# SHABlindController.net
KiCad netlist of a schematic drawn in EAGLE
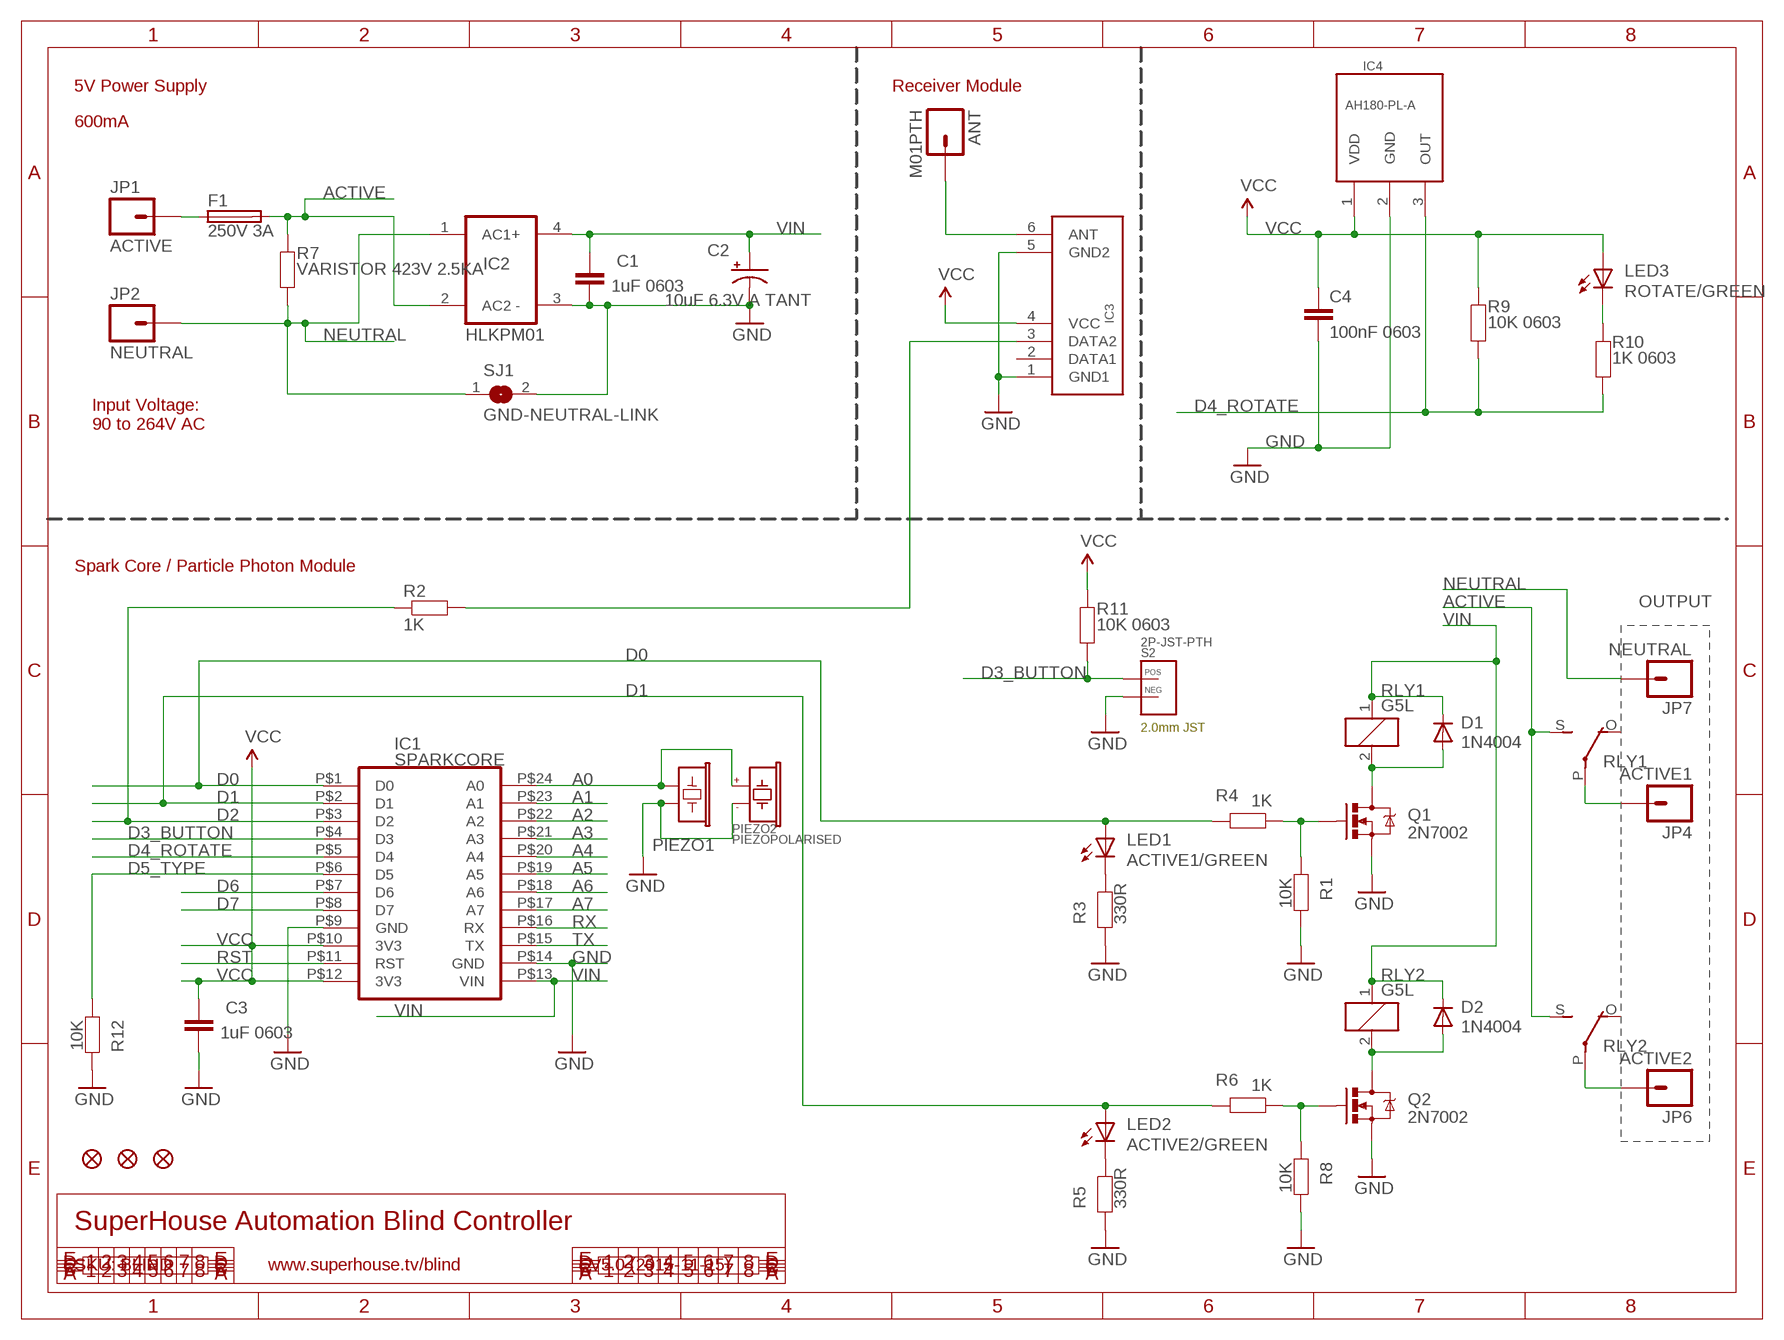
[diagram p0: schematic, sheet 1]

(export (version "E")
  (design (tool "Eeschema 10.0.6"))
  (components
    (comp (ref "ANT")
      (value "M01PTH")
      (footprint "eagle-import:1X01")
      (libsource (lib "eagle-import") (part "M01PTH"))
    )
    (comp (ref "C1")
      (value "1uF 0603")
      (footprint "eagle-import:0603@1")
      (libsource (lib "eagle-import") (part "CAP0603"))
    )
    (comp (ref "C2")
      (value "10uF 6.3V A TANT")
      (footprint "eagle-import:EIA3216")
      (libsource (lib "eagle-import") (part "CAP_POL1206"))
    )
    (comp (ref "C3")
      (value "1uF 0603")
      (footprint "eagle-import:0603@1")
      (libsource (lib "eagle-import") (part "CAP0603"))
    )
    (comp (ref "C4")
      (value "100nF 0603")
      (footprint "eagle-import:0603")
      (libsource (lib "eagle-import") (part "freetronics-master-v1.1_CAP0603"))
    )
    (comp (ref "D1")
      (value "1N4004")
      (footprint "eagle-import:SMB-DIODE")
      (libsource (lib "eagle-import") (part "DIODESMB"))
    )
    (comp (ref "D2")
      (value "1N4004")
      (footprint "eagle-import:SMB-DIODE")
      (libsource (lib "eagle-import") (part "DIODESMB"))
    )
    (comp (ref "F1")
      (value "250V 3A")
      (footprint "eagle-import:PICOFUSE")
      (libsource (lib "eagle-import") (part "PICOFUSEH"))
    )
    (comp (ref "FID1")
      (value "FIDUCIAL1X2.5")
      (footprint "eagle-import:FIDUCIAL-1X2.5")
      (libsource (lib "eagle-import") (part "FIDUCIAL1X2.5"))
    )
    (comp (ref "FID2")
      (value "FIDUCIAL1X2.5")
      (footprint "eagle-import:FIDUCIAL-1X2.5")
      (libsource (lib "eagle-import") (part "FIDUCIAL1X2.5"))
    )
    (comp (ref "FID3")
      (value "FIDUCIAL1X2.5")
      (footprint "eagle-import:FIDUCIAL-1X2.5")
      (libsource (lib "eagle-import") (part "FIDUCIAL1X2.5"))
    )
    (comp (ref "IC1")
      (value "SPARKCORE")
      (footprint "eagle-import:SPARKCORE")
      (libsource (lib "eagle-import") (part "SPARKCORE"))
    )
    (comp (ref "IC2")
      (value "HLKPM01")
      (footprint "eagle-import:HLKPM01")
      (libsource (lib "eagle-import") (part "HLKPM01"))
    )
    (comp (ref "IC3")
      (value "RXB1")
      (footprint "eagle-import:RX-B1-SHORT-FLAT")
      (libsource (lib "eagle-import") (part "RXB1SHORTFLAT"))
    )
    (comp (ref "IC4")
      (value "AH180-PL-A")
      (footprint "eagle-import:TO92FLATUP")
      (libsource (lib "eagle-import") (part "US1881TO92"))
    )
    (comp (ref "JP1")
      (value "ACTIVE")
      (footprint "eagle-import:1X01LARGE")
      (libsource (lib "eagle-import") (part "M01PTH_LARGE"))
    )
    (comp (ref "JP2")
      (value "NEUTRAL")
      (footprint "eagle-import:1X01LARGE")
      (libsource (lib "eagle-import") (part "M01PTH_LARGE"))
    )
    (comp (ref "JP4")
      (value "ACTIVE1")
      (footprint "eagle-import:1X01LARGE")
      (libsource (lib "eagle-import") (part "M01PTH_LARGE"))
    )
    (comp (ref "JP6")
      (value "ACTIVE2")
      (footprint "eagle-import:1X01LARGE")
      (libsource (lib "eagle-import") (part "M01PTH_LARGE"))
    )
    (comp (ref "JP7")
      (value "NEUTRAL")
      (footprint "eagle-import:1X01LARGE")
      (libsource (lib "eagle-import") (part "M01PTH_LARGE"))
    )
    (comp (ref "LED1")
      (value "ACTIVE1/GREEN")
      (footprint "eagle-import:LED-0603")
      (libsource (lib "eagle-import") (part "LED0603"))
    )
    (comp (ref "LED2")
      (value "ACTIVE2/GREEN")
      (footprint "eagle-import:LED-0603")
      (libsource (lib "eagle-import") (part "LED0603"))
    )
    (comp (ref "LED3")
      (value "ROTATE/GREEN")
      (footprint "eagle-import:LED-0603")
      (libsource (lib "eagle-import") (part "LED0603"))
    )
    (comp (ref "PIEZO1")
      (value "BUZZERSMD12X12")
      (footprint "eagle-import:BUZZER-12X12-SMT")
      (libsource (lib "eagle-import") (part "BUZZERSMD12X12"))
    )
    (comp (ref "PIEZO2")
      (value "PIEZOPOLARISED")
      (footprint "eagle-import:PIEZO12MMWIDEPOLARISED")
      (libsource (lib "eagle-import") (part "PIEZOPOLARISED"))
    )
    (comp (ref "Q1")
      (value "2N7002")
      (footprint "eagle-import:SOT23-3")
      (libsource (lib "eagle-import") (part "MOSFET-NCHANNELSMD"))
    )
    (comp (ref "Q2")
      (value "2N7002")
      (footprint "eagle-import:SOT23-3")
      (libsource (lib "eagle-import") (part "MOSFET-NCHANNELSMD"))
    )
    (comp (ref "R1")
      (value "10K")
      (footprint "eagle-import:0603")
      (libsource (lib "eagle-import") (part "RESISTOR0603"))
    )
    (comp (ref "R2")
      (value "1K")
      (footprint "eagle-import:0603")
      (libsource (lib "eagle-import") (part "RESISTOR0603"))
    )
    (comp (ref "R3")
      (value "330R")
      (footprint "eagle-import:0603")
      (libsource (lib "eagle-import") (part "RESISTOR0603"))
    )
    (comp (ref "R4")
      (value "1K")
      (footprint "eagle-import:0603")
      (libsource (lib "eagle-import") (part "RESISTOR0603"))
    )
    (comp (ref "R5")
      (value "330R")
      (footprint "eagle-import:0603")
      (libsource (lib "eagle-import") (part "RESISTOR0603"))
    )
    (comp (ref "R6")
      (value "1K")
      (footprint "eagle-import:0603")
      (libsource (lib "eagle-import") (part "RESISTOR0603"))
    )
    (comp (ref "R7")
      (value "VARISTOR 423V 2.5KA")
      (footprint "eagle-import:AXIAL-0.3")
      (libsource (lib "eagle-import") (part "freetronics-master-v1.1_RESISTORPTH1"))
    )
    (comp (ref "R8")
      (value "10K")
      (footprint "eagle-import:0603")
      (libsource (lib "eagle-import") (part "RESISTOR0603"))
    )
    (comp (ref "R9")
      (value "10K 0603")
      (footprint "eagle-import:0603")
      (libsource (lib "eagle-import") (part "freetronics-master-v1_RESISTOR0603"))
    )
    (comp (ref "R10")
      (value "1K 0603")
      (footprint "eagle-import:0603")
      (libsource (lib "eagle-import") (part "freetronics-master-v1_RESISTOR0603"))
    )
    (comp (ref "R11")
      (value "10K 0603")
      (footprint "eagle-import:0603")
      (libsource (lib "eagle-import") (part "freetronics-master-v1_RESISTOR0603"))
    )
    (comp (ref "R12")
      (value "10K")
      (footprint "eagle-import:0603")
      (libsource (lib "eagle-import") (part "RESISTOR0603"))
    )
    (comp (ref "RLY1")
      (value "G5L")
      (footprint "eagle-import:G5LE")
      (libsource (lib "eagle-import") (part "G5L"))
    )
    (comp (ref "RLY2")
      (value "G5L")
      (footprint "eagle-import:G5LE")
      (libsource (lib "eagle-import") (part "G5L"))
    )
    (comp (ref "S2")
      (value "2P-JST-PTH")
      (footprint "eagle-import:JST-2MM-TH-RA")
      (libsource (lib "eagle-import") (part "2P-JST-TH-RAPTH"))
    )
    (comp (ref "SJ1")
      (value "GND-NEUTRAL-LINK")
      (footprint "eagle-import:SJ")
      (libsource (lib "eagle-import") (part "SJ"))
    )
  )
  (nets
    (net (code "1") (name "/A0") (class "Default")
      (node (ref "IC1") (pin "P$24") (pinfunction "A0_P$24") (pintype "bidirectional"))
      (node (ref "PIEZO1") (pin "1") (pinfunction "1_1") (pintype "passive"))
      (node (ref "PIEZO2") (pin "1") (pinfunction "+_1") (pintype "bidirectional"))
    )
    (net (code "2") (name "/A1") (class "Default")
      (node (ref "IC1") (pin "P$23") (pinfunction "A1_P$23") (pintype "bidirectional"))
    )
    (net (code "3") (name "/A2") (class "Default")
      (node (ref "IC1") (pin "P$22") (pinfunction "A2_P$22") (pintype "bidirectional"))
    )
    (net (code "4") (name "/A3") (class "Default")
      (node (ref "IC1") (pin "P$21") (pinfunction "A3_P$21") (pintype "bidirectional"))
    )
    (net (code "5") (name "/A4") (class "Default")
      (node (ref "IC1") (pin "P$20") (pinfunction "A4_P$20") (pintype "bidirectional"))
    )
    (net (code "6") (name "/A5") (class "Default")
      (node (ref "IC1") (pin "P$19") (pinfunction "A5_P$19") (pintype "bidirectional"))
    )
    (net (code "7") (name "/A6") (class "Default")
      (node (ref "IC1") (pin "P$18") (pinfunction "A6_P$18") (pintype "bidirectional"))
    )
    (net (code "8") (name "/A7") (class "Default")
      (node (ref "IC1") (pin "P$17") (pinfunction "A7_P$17") (pintype "bidirectional"))
    )
    (net (code "9") (name "/ACTIVE") (class "Default")
      (node (ref "F1") (pin "2") (pinfunction "2_2") (pintype "passive"))
      (node (ref "IC2") (pin "2") (pinfunction "AC2_2") (pintype "bidirectional"))
      (node (ref "R7") (pin "P$2") (pinfunction "2_P$2") (pintype "passive"))
      (node (ref "RLY1") (pin "S") (pinfunction "S_S") (pintype "passive"))
      (node (ref "RLY2") (pin "S") (pinfunction "S_S") (pintype "passive"))
    )
    (net (code "10") (name "/D0") (class "Default")
      (node (ref "IC1") (pin "P$1") (pinfunction "D0_P$1") (pintype "bidirectional"))
      (node (ref "LED1") (pin "A") (pinfunction "A_A") (pintype "passive"))
      (node (ref "R4") (pin "2") (pinfunction "2_2") (pintype "passive"))
    )
    (net (code "11") (name "/D1") (class "Default")
      (node (ref "IC1") (pin "P$2") (pinfunction "D1_P$2") (pintype "bidirectional"))
      (node (ref "LED2") (pin "A") (pinfunction "A_A") (pintype "passive"))
      (node (ref "R6") (pin "2") (pinfunction "2_2") (pintype "passive"))
    )
    (net (code "12") (name "/D2") (class "Default")
      (node (ref "IC1") (pin "P$3") (pinfunction "D2_P$3") (pintype "bidirectional"))
      (node (ref "R2") (pin "1") (pinfunction "1_1") (pintype "passive"))
    )
    (net (code "13") (name "/D3_BUTTON") (class "Default")
      (node (ref "IC1") (pin "P$4") (pinfunction "D3_P$4") (pintype "bidirectional"))
      (node (ref "R11") (pin "1") (pinfunction "1_1") (pintype "passive"))
      (node (ref "S2") (pin "POS") (pinfunction "POS_POS") (pintype "power_in"))
    )
    (net (code "14") (name "/D4_ROTATE") (class "Default")
      (node (ref "IC1") (pin "P$5") (pinfunction "D4_P$5") (pintype "bidirectional"))
      (node (ref "IC4") (pin "3") (pinfunction "OUT_3") (pintype "output"))
      (node (ref "R10") (pin "2") (pinfunction "2_2") (pintype "passive"))
      (node (ref "R9") (pin "1") (pinfunction "1_1") (pintype "passive"))
    )
    (net (code "15") (name "/D5_TYPE") (class "Default")
      (node (ref "IC1") (pin "P$6") (pinfunction "D5_P$6") (pintype "bidirectional"))
      (node (ref "R12") (pin "1") (pinfunction "1_1") (pintype "passive"))
    )
    (net (code "16") (name "/D6") (class "Default")
      (node (ref "IC1") (pin "P$7") (pinfunction "D6_P$7") (pintype "bidirectional"))
    )
    (net (code "17") (name "/D7") (class "Default")
      (node (ref "IC1") (pin "P$8") (pinfunction "D7_P$8") (pintype "bidirectional"))
    )
    (net (code "18") (name "/NEUTRAL") (class "Default")
      (node (ref "IC2") (pin "1") (pinfunction "AC1_1") (pintype "bidirectional"))
      (node (ref "JP2") (pin "1") (pinfunction "1_1") (pintype "passive"))
      (node (ref "JP7") (pin "1") (pinfunction "1_1") (pintype "passive"))
      (node (ref "R7") (pin "P$1") (pinfunction "1_P$1") (pintype "passive"))
      (node (ref "SJ1") (pin "1") (pinfunction "1_1") (pintype "passive"))
    )
    (net (code "19") (name "/RST") (class "Default")
      (node (ref "IC1") (pin "P$11") (pinfunction "RST_P$11") (pintype "bidirectional"))
    )
    (net (code "20") (name "/RX") (class "Default")
      (node (ref "IC1") (pin "P$16") (pinfunction "RX_P$16") (pintype "bidirectional"))
    )
    (net (code "21") (name "/TX") (class "Default")
      (node (ref "IC1") (pin "P$15") (pinfunction "TX_P$15") (pintype "bidirectional"))
    )
    (net (code "22") (name "/VIN") (class "Default")
      (node (ref "C1") (pin "1") (pinfunction "1_1") (pintype "passive"))
      (node (ref "C2") (pin "A") (pinfunction "+_A") (pintype "passive"))
      (node (ref "D1") (pin "C") (pinfunction "C_C") (pintype "passive"))
      (node (ref "D2") (pin "C") (pinfunction "C_C") (pintype "passive"))
      (node (ref "IC1") (pin "P$13") (pinfunction "VIN_P$13") (pintype "bidirectional"))
      (node (ref "IC2") (pin "4") (pinfunction "+_4") (pintype "bidirectional"))
      (node (ref "RLY1") (pin "1") (pinfunction "1_1") (pintype "passive"))
      (node (ref "RLY2") (pin "1") (pinfunction "1_1") (pintype "passive"))
    )
    (net (code "23") (name "GND") (class "Default")
      (node (ref "C1") (pin "2") (pinfunction "2_2") (pintype "passive"))
      (node (ref "C2") (pin "C") (pinfunction "-_C") (pintype "passive"))
      (node (ref "C3") (pin "2") (pinfunction "2_2") (pintype "passive"))
      (node (ref "C4") (pin "2") (pinfunction "2_2") (pintype "passive"))
      (node (ref "IC1") (pin "P$14") (pinfunction "GND_P$14") (pintype "bidirectional"))
      (node (ref "IC1") (pin "P$9") (pinfunction "GND_P$9") (pintype "bidirectional"))
      (node (ref "IC2") (pin "3") (pinfunction "-_3") (pintype "bidirectional"))
      (node (ref "IC3") (pin "1") (pinfunction "GND1_1") (pintype "bidirectional"))
      (node (ref "IC3") (pin "5") (pinfunction "GND2_5") (pintype "bidirectional"))
      (node (ref "IC4") (pin "2") (pinfunction "GND_2") (pintype "power_in"))
      (node (ref "PIEZO1") (pin "2") (pinfunction "2_2") (pintype "passive"))
      (node (ref "PIEZO2") (pin "2") (pinfunction "-_2") (pintype "bidirectional"))
      (node (ref "Q1") (pin "2") (pinfunction "S_2") (pintype "passive"))
      (node (ref "Q2") (pin "2") (pinfunction "S_2") (pintype "passive"))
      (node (ref "R1") (pin "2") (pinfunction "2_2") (pintype "passive"))
      (node (ref "R12") (pin "2") (pinfunction "2_2") (pintype "passive"))
      (node (ref "R3") (pin "1") (pinfunction "1_1") (pintype "passive"))
      (node (ref "R5") (pin "1") (pinfunction "1_1") (pintype "passive"))
      (node (ref "R8") (pin "2") (pinfunction "2_2") (pintype "passive"))
      (node (ref "S2") (pin "NEG") (pinfunction "NEG_NEG") (pintype "power_in"))
      (node (ref "SJ1") (pin "2") (pinfunction "2_2") (pintype "passive"))
    )
    (net (code "24") (name "Net-(F1-Pad1)") (class "Default")
      (node (ref "F1") (pin "1") (pinfunction "1_1") (pintype "passive"))
      (node (ref "JP1") (pin "1") (pinfunction "1_1") (pintype "passive"))
    )
    (net (code "25") (name "Net-(IC3-ANT)") (class "Default")
      (node (ref "ANT") (pin "1") (pinfunction "1_1") (pintype "passive"))
      (node (ref "IC3") (pin "6") (pinfunction "ANT_6") (pintype "bidirectional"))
    )
    (net (code "26") (name "Net-(IC3-DATA2)") (class "Default")
      (node (ref "IC3") (pin "3") (pinfunction "DATA2_3") (pintype "bidirectional"))
      (node (ref "R2") (pin "2") (pinfunction "2_2") (pintype "passive"))
    )
    (net (code "27") (name "Net-(JP4-Pad1)") (class "Default")
      (node (ref "JP4") (pin "1") (pinfunction "1_1") (pintype "passive"))
      (node (ref "RLY1") (pin "P") (pinfunction "P_P") (pintype "passive"))
    )
    (net (code "28") (name "Net-(JP6-Pad1)") (class "Default")
      (node (ref "JP6") (pin "1") (pinfunction "1_1") (pintype "passive"))
      (node (ref "RLY2") (pin "P") (pinfunction "P_P") (pintype "passive"))
    )
    (net (code "29") (name "Net-(LED1-PadC)") (class "Default")
      (node (ref "LED1") (pin "C") (pinfunction "C_C") (pintype "passive"))
      (node (ref "R3") (pin "2") (pinfunction "2_2") (pintype "passive"))
    )
    (net (code "30") (name "Net-(LED2-PadC)") (class "Default")
      (node (ref "LED2") (pin "C") (pinfunction "C_C") (pintype "passive"))
      (node (ref "R5") (pin "2") (pinfunction "2_2") (pintype "passive"))
    )
    (net (code "31") (name "Net-(LED3-PadC)") (class "Default")
      (node (ref "LED3") (pin "C") (pinfunction "C_C") (pintype "passive"))
      (node (ref "R10") (pin "1") (pinfunction "1_1") (pintype "passive"))
    )
    (net (code "32") (name "Net-(Q1-D)") (class "Default")
      (node (ref "D1") (pin "A") (pinfunction "A_A") (pintype "passive"))
      (node (ref "Q1") (pin "3") (pinfunction "D_3") (pintype "passive"))
      (node (ref "RLY1") (pin "2") (pinfunction "2_2") (pintype "passive"))
    )
    (net (code "33") (name "Net-(Q1-G)") (class "Default")
      (node (ref "Q1") (pin "1") (pinfunction "G_1") (pintype "passive"))
      (node (ref "R1") (pin "1") (pinfunction "1_1") (pintype "passive"))
      (node (ref "R4") (pin "1") (pinfunction "1_1") (pintype "passive"))
    )
    (net (code "34") (name "Net-(Q2-D)") (class "Default")
      (node (ref "D2") (pin "A") (pinfunction "A_A") (pintype "passive"))
      (node (ref "Q2") (pin "3") (pinfunction "D_3") (pintype "passive"))
      (node (ref "RLY2") (pin "2") (pinfunction "2_2") (pintype "passive"))
    )
    (net (code "35") (name "Net-(Q2-G)") (class "Default")
      (node (ref "Q2") (pin "1") (pinfunction "G_1") (pintype "passive"))
      (node (ref "R6") (pin "1") (pinfunction "1_1") (pintype "passive"))
      (node (ref "R8") (pin "1") (pinfunction "1_1") (pintype "passive"))
    )
    (net (code "36") (name "VCC") (class "Default")
      (node (ref "C3") (pin "1") (pinfunction "1_1") (pintype "passive"))
      (node (ref "C4") (pin "1") (pinfunction "1_1") (pintype "passive"))
      (node (ref "IC1") (pin "P$10") (pinfunction "3V3_P$10") (pintype "bidirectional"))
      (node (ref "IC1") (pin "P$12") (pinfunction "3V3_P$12") (pintype "bidirectional"))
      (node (ref "IC3") (pin "4") (pinfunction "VCC_4") (pintype "bidirectional"))
      (node (ref "IC4") (pin "1") (pinfunction "VDD_1") (pintype "power_in"))
      (node (ref "LED3") (pin "A") (pinfunction "A_A") (pintype "passive"))
      (node (ref "R11") (pin "2") (pinfunction "2_2") (pintype "passive"))
      (node (ref "R9") (pin "2") (pinfunction "2_2") (pintype "passive"))
    )
    (net (code "37") (name "unconnected-(IC3-DATA1-Pad2)") (class "Default")
      (node (ref "IC3") (pin "2") (pinfunction "DATA1_2") (pintype "bidirectional"))
    )
    (net (code "38") (name "unconnected-(RLY1-PadO)") (class "Default")
      (node (ref "RLY1") (pin "O") (pinfunction "O_O") (pintype "passive"))
    )
    (net (code "39") (name "unconnected-(RLY2-PadO)") (class "Default")
      (node (ref "RLY2") (pin "O") (pinfunction "O_O") (pintype "passive"))
    )
  )
)
